# Sheet1.net
KiCad netlist of a schematic drawn in Altium Designer
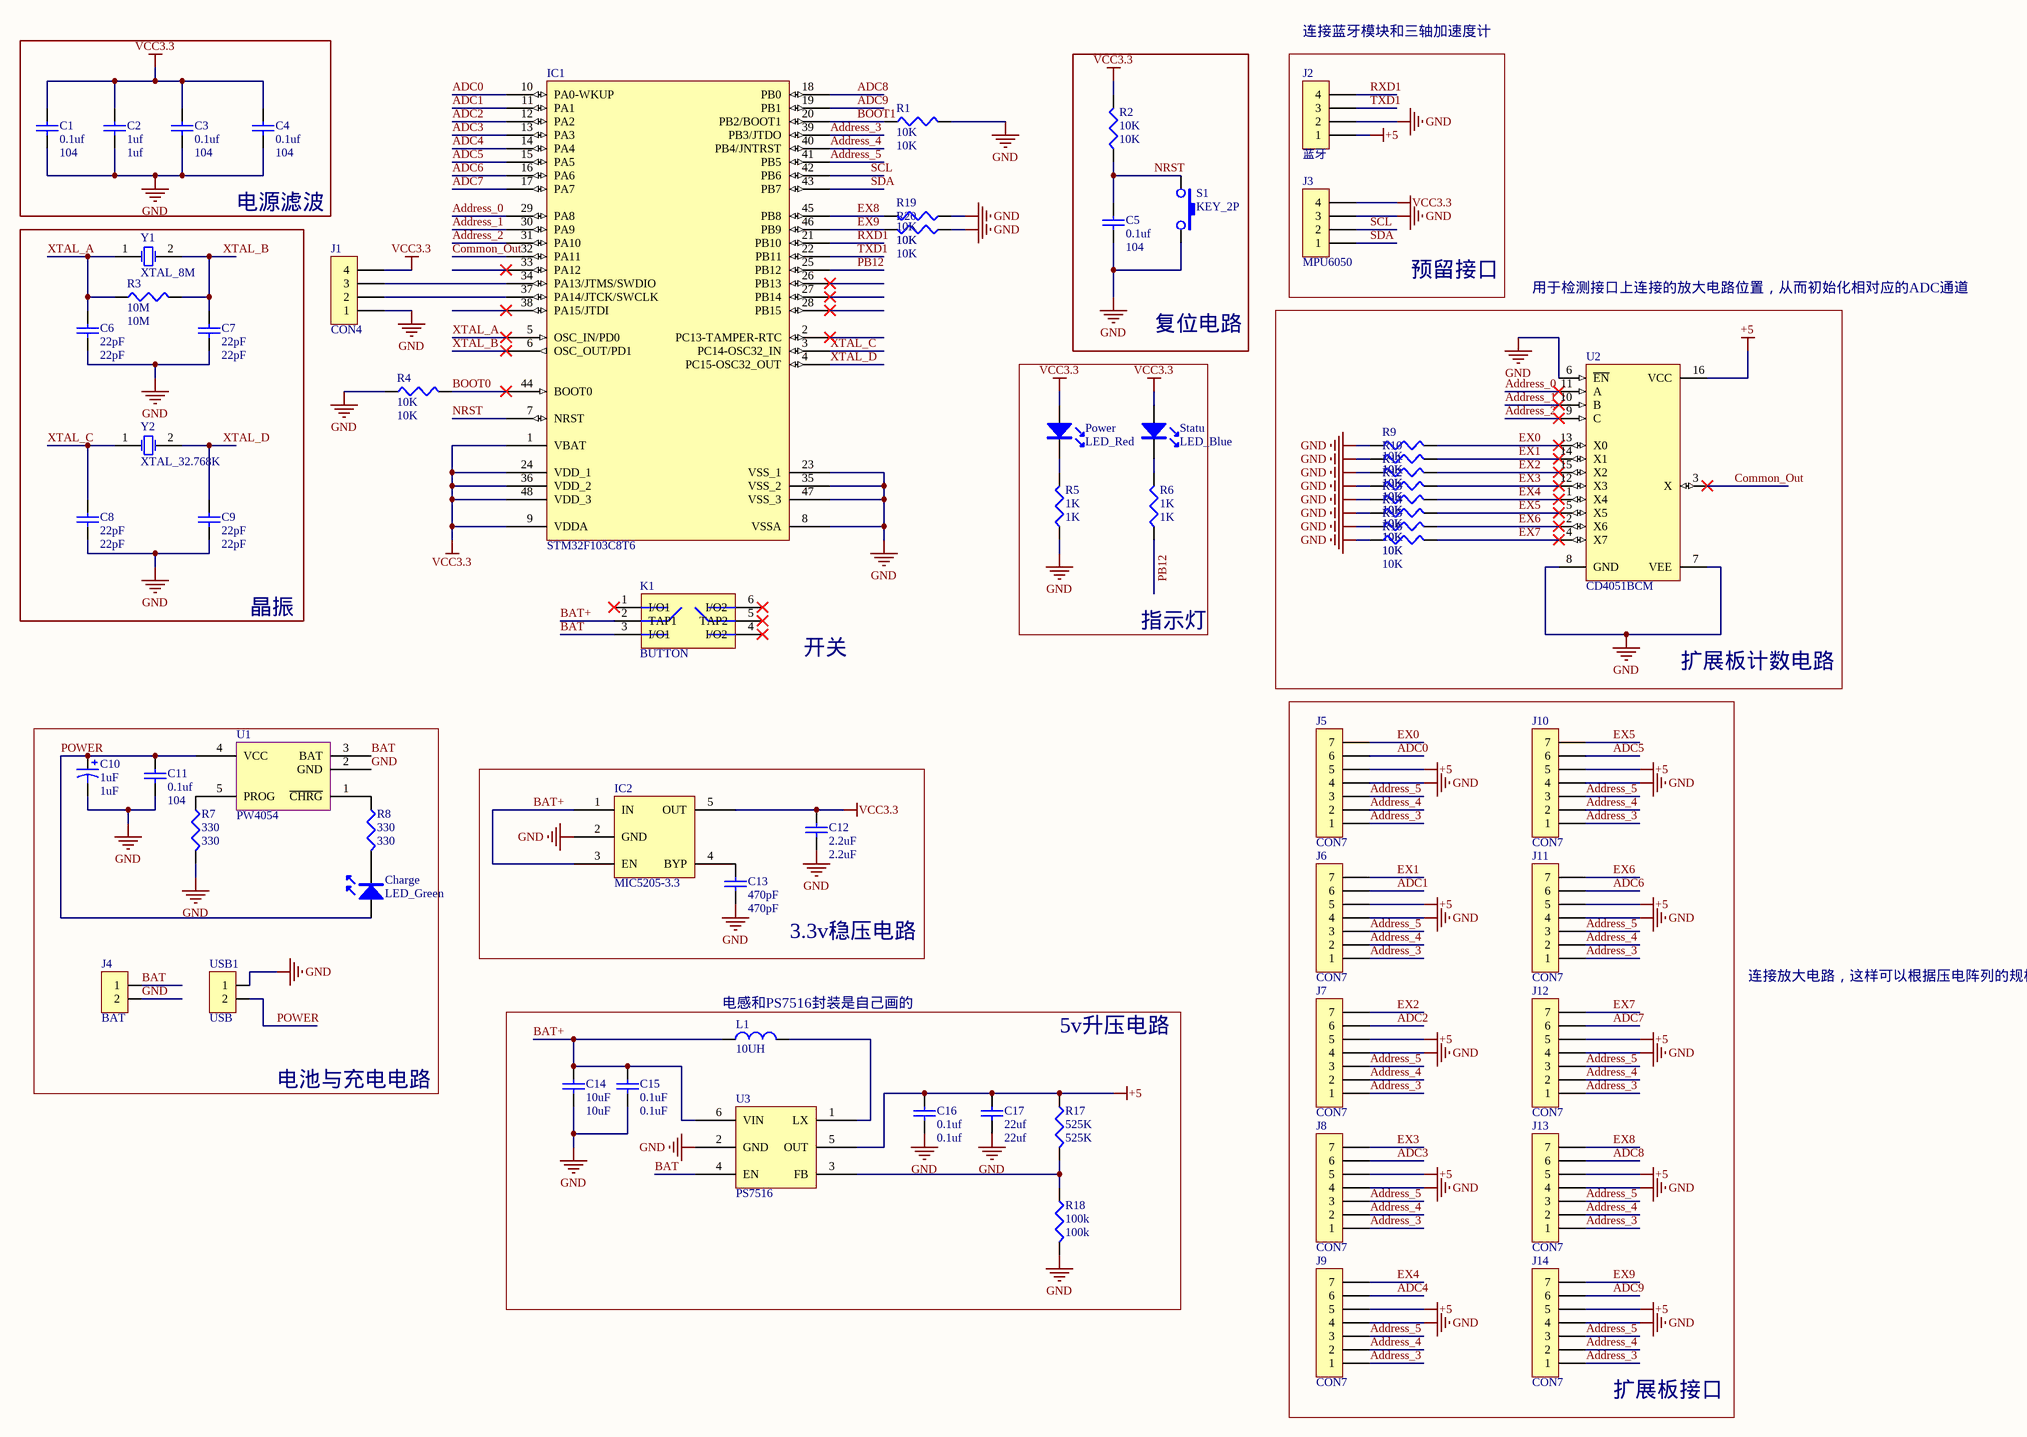
[diagram p0: Sheet1.SchDoc]

(export (version "E")
  (design (tool "Eeschema 10.0.6"))
  (components
    (comp (ref "C1")
      (value "0.1uf")
      (footprint "6-0805_L")
      (description "Capacitor (Semiconductor SIM Model)")
      (fields (field (name "ALTIUM_VALUE") "104") (field (name "PUBLISHER") "Altium Limited"))
      (libsource (lib "Miscellaneous Devices") (part "Cap Semi"))
    )
    (comp (ref "C2")
      (value "1uf")
      (footprint "6-0805_L")
      (description "Capacitor (Semiconductor SIM Model)")
      (fields (field (name "ALTIUM_VALUE") "1uf") (field (name "PUBLISHER") "Altium Limited"))
      (libsource (lib "Miscellaneous Devices") (part "Cap Semi"))
    )
    (comp (ref "C3")
      (value "0.1uf")
      (footprint "6-0805_L")
      (description "Capacitor (Semiconductor SIM Model)")
      (fields (field (name "ALTIUM_VALUE") "104") (field (name "PUBLISHER") "Altium Limited"))
      (libsource (lib "Miscellaneous Devices") (part "Cap Semi"))
    )
    (comp (ref "C4")
      (value "0.1uf")
      (footprint "6-0805_L")
      (description "Capacitor (Semiconductor SIM Model)")
      (fields (field (name "ALTIUM_VALUE") "104") (field (name "PUBLISHER") "Altium Limited"))
      (libsource (lib "Miscellaneous Devices") (part "Cap Semi"))
    )
    (comp (ref "C5")
      (value "0.1uf")
      (footprint "6-0805_L")
      (description "Capacitor (Semiconductor SIM Model)")
      (fields (field (name "ALTIUM_VALUE") "104") (field (name "PUBLISHER") "Altium Limited"))
      (libsource (lib "Miscellaneous Devices") (part "Cap Semi"))
    )
    (comp (ref "C6")
      (value "22pF")
      (footprint "6-0805_L")
      (description "Capacitor (Semiconductor SIM Model)")
      (fields (field (name "ALTIUM_VALUE") "22pF") (field (name "PUBLISHER") "Altium Limited"))
      (libsource (lib "Miscellaneous Devices") (part "Cap Semi"))
    )
    (comp (ref "C7")
      (value "22pF")
      (footprint "6-0805_L")
      (description "Capacitor (Semiconductor SIM Model)")
      (fields (field (name "ALTIUM_VALUE") "22pF") (field (name "PUBLISHER") "Altium Limited"))
      (libsource (lib "Miscellaneous Devices") (part "Cap Semi"))
    )
    (comp (ref "C8")
      (value "22pF")
      (footprint "6-0805_L")
      (description "Capacitor (Semiconductor SIM Model)")
      (fields (field (name "ALTIUM_VALUE") "22pF") (field (name "PUBLISHER") "Altium Limited"))
      (libsource (lib "Miscellaneous Devices") (part "Cap Semi"))
    )
    (comp (ref "C9")
      (value "22pF")
      (footprint "6-0805_L")
      (description "Capacitor (Semiconductor SIM Model)")
      (fields (field (name "ALTIUM_VALUE") "22pF") (field (name "PUBLISHER") "Altium Limited"))
      (libsource (lib "Miscellaneous Devices") (part "Cap Semi"))
    )
    (comp (ref "C10")
      (value "1uF")
      (footprint "C0805")
      (description "Polarized Capacitor (Surface Mount)")
      (fields (field (name "ALTIUM_VALUE") "1uF") (field (name "PUBLISHER") "Altium Limited"))
      (libsource (lib "Miscellaneous Devices") (part "Cap Pol3"))
    )
    (comp (ref "C11")
      (value "0.1uf")
      (footprint "6-0805_L")
      (description "Capacitor (Semiconductor SIM Model)")
      (fields (field (name "ALTIUM_VALUE") "104") (field (name "PUBLISHER") "Altium Limited"))
      (libsource (lib "Miscellaneous Devices") (part "Cap Semi"))
    )
    (comp (ref "C12")
      (value "2.2uF")
      (footprint "6-0805_L")
      (description "Capacitor (Semiconductor SIM Model)")
      (fields (field (name "ALTIUM_VALUE") "2.2uF") (field (name "PUBLISHER") "Altium Limited"))
      (libsource (lib "Miscellaneous Devices") (part "Cap Semi"))
    )
    (comp (ref "C13")
      (value "470pF")
      (footprint "6-0805_L")
      (description "Capacitor (Semiconductor SIM Model)")
      (fields (field (name "ALTIUM_VALUE") "470pF") (field (name "PUBLISHER") "Altium Limited"))
      (libsource (lib "Miscellaneous Devices") (part "Cap Semi"))
    )
    (comp (ref "C14")
      (value "10uF")
      (footprint "6-0805_L")
      (description "Capacitor (Semiconductor SIM Model)")
      (fields (field (name "ALTIUM_VALUE") "10uF") (field (name "PUBLISHER") "Altium Limited"))
      (libsource (lib "Miscellaneous Devices") (part "Cap Semi"))
    )
    (comp (ref "C15")
      (value "0.1uF")
      (footprint "6-0805_L")
      (description "Capacitor (Semiconductor SIM Model)")
      (fields (field (name "ALTIUM_VALUE") "0.1uF") (field (name "PUBLISHER") "Altium Limited"))
      (libsource (lib "Miscellaneous Devices") (part "Cap Semi"))
    )
    (comp (ref "C16")
      (value "0.1uf")
      (footprint "6-0805_L")
      (description "Capacitor (Semiconductor SIM Model)")
      (fields (field (name "ALTIUM_VALUE") "0.1uf") (field (name "PUBLISHER") "Altium Limited"))
      (libsource (lib "Miscellaneous Devices") (part "Cap Semi"))
    )
    (comp (ref "C17")
      (value "22uf")
      (footprint "6-0805_L")
      (description "Capacitor (Semiconductor SIM Model)")
      (fields (field (name "ALTIUM_VALUE") "22uf") (field (name "PUBLISHER") "Altium Limited"))
      (libsource (lib "Miscellaneous Devices") (part "Cap Semi"))
    )
    (comp (ref "Charge")
      (value "LED_Green")
      (footprint "6-0805_M")
      (description "LED")
      (libsource (lib "Component") (part "LED"))
    )
    (comp (ref "IC1")
      (value "STM32F103C8T6")
      (footprint "LQFP48")
      (description "单片机")
      (fields (field (name "PUBLISHER") "Altium Limited"))
      (libsource (lib "Chip") (part "STM32F103C8T6"))
    )
    (comp (ref "IC2")
      (value "MIC5205-3.3")
      (footprint "SOT-23-5")
      (description "稳压")
      (libsource (lib "Chip") (part "MIC5205-3.3"))
    )
    (comp (ref "J1")
      (value "CON4")
      (footprint "HDR1X4")
      (description "连接器")
      (libsource (lib "Connector") (part "CON4"))
    )
    (comp (ref "J2")
      (value "蓝牙")
      (footprint "HDR1X4")
      (description "Connector")
      (libsource (lib "杂元件库") (part "CON4"))
    )
    (comp (ref "J3")
      (value "MPU6050")
      (footprint "HDR1X4")
      (description "Connector")
      (libsource (lib "杂元件库") (part "CON4"))
    )
    (comp (ref "J4")
      (value "BAT")
      (footprint "HDR1X2")
      (description "Conjunctor")
      (libsource (lib "zj") (part "CON2"))
    )
    (comp (ref "J5")
      (value "CON7")
      (footprint "8P软排线")
      (description "Connector")
      (libsource (lib "杂元件库") (part "CON7"))
    )
    (comp (ref "J6")
      (value "CON7")
      (footprint "8P软排线")
      (description "Connector")
      (libsource (lib "杂元件库") (part "CON7"))
    )
    (comp (ref "J7")
      (value "CON7")
      (footprint "8P软排线")
      (description "Connector")
      (libsource (lib "杂元件库") (part "CON7"))
    )
    (comp (ref "J8")
      (value "CON7")
      (footprint "8P软排线")
      (description "Connector")
      (libsource (lib "杂元件库") (part "CON7"))
    )
    (comp (ref "J9")
      (value "CON7")
      (footprint "8P软排线")
      (description "Connector")
      (libsource (lib "杂元件库") (part "CON7"))
    )
    (comp (ref "J10")
      (value "CON7")
      (footprint "8P软排线")
      (description "Connector")
      (libsource (lib "杂元件库") (part "CON7"))
    )
    (comp (ref "J11")
      (value "CON7")
      (footprint "8P软排线")
      (description "Connector")
      (libsource (lib "杂元件库") (part "CON7"))
    )
    (comp (ref "J12")
      (value "CON7")
      (footprint "8P软排线")
      (description "Connector")
      (libsource (lib "杂元件库") (part "CON7"))
    )
    (comp (ref "J13")
      (value "CON7")
      (footprint "8P软排线")
      (description "Connector")
      (libsource (lib "杂元件库") (part "CON7"))
    )
    (comp (ref "J14")
      (value "CON7")
      (footprint "8P软排线")
      (description "Connector")
      (libsource (lib "杂元件库") (part "CON7"))
    )
    (comp (ref "K1")
      (value "BUTTON")
      (footprint "My:switch")
      (description "自锁按键")
      (libsource (lib "Component") (part "BUTTON"))
    )
    (comp (ref "L1")
      (value "10UH")
      (footprint "0850")
      (description "电感")
      (libsource (lib "Component") (part "Inductor"))
    )
    (comp (ref "Power")
      (value "LED_Red")
      (footprint "6-0805_M")
      (description "LED")
      (libsource (lib "Component") (part "LED"))
    )
    (comp (ref "R1")
      (value "10K")
      (footprint "6-0805_L")
      (description "Resistor")
      (fields (field (name "ALTIUM_VALUE") "10K") (field (name "PUBLISHER") "Altium Limited"))
      (libsource (lib "Miscellaneous Devices") (part "Res3"))
    )
    (comp (ref "R2")
      (value "10K")
      (footprint "6-0805_L")
      (description "Resistor")
      (fields (field (name "ALTIUM_VALUE") "10K") (field (name "PUBLISHER") "Altium Limited"))
      (libsource (lib "Miscellaneous Devices") (part "Res3"))
    )
    (comp (ref "R3")
      (value "10M")
      (footprint "6-0805_L")
      (description "Resistor")
      (fields (field (name "ALTIUM_VALUE") "10M") (field (name "PUBLISHER") "Altium Limited"))
      (libsource (lib "Miscellaneous Devices") (part "Res3"))
    )
    (comp (ref "R4")
      (value "10K")
      (footprint "6-0805_L")
      (description "Resistor")
      (fields (field (name "ALTIUM_VALUE") "10K") (field (name "PUBLISHER") "Altium Limited"))
      (libsource (lib "Miscellaneous Devices") (part "Res3"))
    )
    (comp (ref "R5")
      (value "1K")
      (footprint "6-0805_L")
      (description "Resistor")
      (fields (field (name "ALTIUM_VALUE") "1K") (field (name "PUBLISHER") "Altium Limited"))
      (libsource (lib "Miscellaneous Devices") (part "Res3"))
    )
    (comp (ref "R6")
      (value "1K")
      (footprint "6-0805_L")
      (description "Resistor")
      (fields (field (name "ALTIUM_VALUE") "1K") (field (name "PUBLISHER") "Altium Limited"))
      (libsource (lib "Miscellaneous Devices") (part "Res3"))
    )
    (comp (ref "R7")
      (value "330")
      (footprint "6-0805_L")
      (description "Resistor")
      (fields (field (name "ALTIUM_VALUE") "330") (field (name "PUBLISHER") "Altium Limited"))
      (libsource (lib "Miscellaneous Devices") (part "Res3"))
    )
    (comp (ref "R8")
      (value "330")
      (footprint "6-0805_L")
      (description "Resistor")
      (fields (field (name "ALTIUM_VALUE") "330") (field (name "PUBLISHER") "Altium Limited"))
      (libsource (lib "Miscellaneous Devices") (part "Res3"))
    )
    (comp (ref "R9")
      (value "10K")
      (footprint "6-0805_L")
      (description "Resistor")
      (fields (field (name "ALTIUM_VALUE") "10K") (field (name "PUBLISHER") "Altium Limited"))
      (libsource (lib "Miscellaneous Devices") (part "Res3"))
    )
    (comp (ref "R10")
      (value "10K")
      (footprint "6-0805_L")
      (description "Resistor")
      (fields (field (name "ALTIUM_VALUE") "10K") (field (name "PUBLISHER") "Altium Limited"))
      (libsource (lib "Miscellaneous Devices") (part "Res3"))
    )
    (comp (ref "R11")
      (value "10K")
      (footprint "6-0805_L")
      (description "Resistor")
      (fields (field (name "ALTIUM_VALUE") "10K") (field (name "PUBLISHER") "Altium Limited"))
      (libsource (lib "Miscellaneous Devices") (part "Res3"))
    )
    (comp (ref "R12")
      (value "10K")
      (footprint "6-0805_L")
      (description "Resistor")
      (fields (field (name "ALTIUM_VALUE") "10K") (field (name "PUBLISHER") "Altium Limited"))
      (libsource (lib "Miscellaneous Devices") (part "Res3"))
    )
    (comp (ref "R13")
      (value "10K")
      (footprint "6-0805_L")
      (description "Resistor")
      (fields (field (name "ALTIUM_VALUE") "10K") (field (name "PUBLISHER") "Altium Limited"))
      (libsource (lib "Miscellaneous Devices") (part "Res3"))
    )
    (comp (ref "R14")
      (value "10K")
      (footprint "6-0805_L")
      (description "Resistor")
      (fields (field (name "ALTIUM_VALUE") "10K") (field (name "PUBLISHER") "Altium Limited"))
      (libsource (lib "Miscellaneous Devices") (part "Res3"))
    )
    (comp (ref "R15")
      (value "10K")
      (footprint "6-0805_L")
      (description "Resistor")
      (fields (field (name "ALTIUM_VALUE") "10K") (field (name "PUBLISHER") "Altium Limited"))
      (libsource (lib "Miscellaneous Devices") (part "Res3"))
    )
    (comp (ref "R16")
      (value "10K")
      (footprint "6-0805_L")
      (description "Resistor")
      (fields (field (name "ALTIUM_VALUE") "10K") (field (name "PUBLISHER") "Altium Limited"))
      (libsource (lib "Miscellaneous Devices") (part "Res3"))
    )
    (comp (ref "R17")
      (value "525K")
      (footprint "6-0805_L")
      (description "Resistor")
      (fields (field (name "ALTIUM_VALUE") "525K") (field (name "PUBLISHER") "Altium Limited"))
      (libsource (lib "Miscellaneous Devices") (part "Res3"))
    )
    (comp (ref "R18")
      (value "100k")
      (footprint "6-0805_L")
      (description "Resistor")
      (fields (field (name "ALTIUM_VALUE") "100k") (field (name "PUBLISHER") "Altium Limited"))
      (libsource (lib "Miscellaneous Devices") (part "Res3"))
    )
    (comp (ref "R19")
      (value "10K")
      (footprint "6-0805_L")
      (description "Resistor")
      (fields (field (name "ALTIUM_VALUE") "10K") (field (name "PUBLISHER") "Altium Limited"))
      (libsource (lib "Miscellaneous Devices") (part "Res3"))
    )
    (comp (ref "R20")
      (value "10K")
      (footprint "6-0805_L")
      (description "Resistor")
      (fields (field (name "ALTIUM_VALUE") "10K") (field (name "PUBLISHER") "Altium Limited"))
      (libsource (lib "Miscellaneous Devices") (part "Res3"))
    )
    (comp (ref "S1")
      (value "KEY_2P")
      (footprint "My:button")
      (description "轻触按键2P")
      (libsource (lib "Component") (part "KEY_2P"))
    )
    (comp (ref "Statu")
      (value "LED_Blue")
      (footprint "6-0805_M")
      (description "LED")
      (libsource (lib "Component") (part "LED"))
    )
    (comp (ref "U1") (value "PW4054") (footprint "SOT-23-CT5_L") (libsource (lib "Schlib") (part "PW4054")))
    (comp (ref "U2")
      (value "CD4051BCM")
      (footprint "M16A_N")
      (description "8-Channel Analog Multiplexer/Demultiplexer")
      (fields (field (name "PUBLISHER") "Altium Limited"))
      (libsource (lib "altium-import") (part "root_0_CD4051BCM_"))
    )
    (comp (ref "U3")
      (value "PS7516")
      (footprint "SOT23-6_M")
      (libsource (lib "Integrated_Library1") (part "PS7516"))
    )
    (comp (ref "USB1")
      (value "USB")
      (footprint "Type-C")
      (description "Conjunctor")
      (libsource (lib "zj") (part "CON2"))
    )
    (comp (ref "Y1")
      (value "XTAL_8M")
      (footprint "xtal")
      (description "Crystal Oscillator")
      (fields (field (name "PUBLISHER") "Altium Limited"))
      (libsource (lib "Miscellaneous Devices") (part "XTAL"))
    )
    (comp (ref "Y2")
      (value "XTAL_32.768K")
      (footprint "R38")
      (description "Crystal Oscillator")
      (fields (field (name "PUBLISHER") "Altium Limited"))
      (libsource (lib "Miscellaneous Devices") (part "XTAL"))
    )
  )
  (nets
    (net (code "1") (name "+5") (class "Default")
      (node (ref "C16") (pin "2") (pinfunction "2_2") (pintype "passive"))
      (node (ref "C17") (pin "2") (pinfunction "2_2") (pintype "passive"))
      (node (ref "J10") (pin "5") (pinfunction "5_5") (pintype "passive"))
      (node (ref "J11") (pin "5") (pinfunction "5_5") (pintype "passive"))
      (node (ref "J12") (pin "5") (pinfunction "5_5") (pintype "passive"))
      (node (ref "J13") (pin "5") (pinfunction "5_5") (pintype "passive"))
      (node (ref "J14") (pin "5") (pinfunction "5_5") (pintype "passive"))
      (node (ref "J2") (pin "1") (pinfunction "1_1") (pintype "passive"))
      (node (ref "J5") (pin "5") (pinfunction "5_5") (pintype "passive"))
      (node (ref "J6") (pin "5") (pinfunction "5_5") (pintype "passive"))
      (node (ref "J7") (pin "5") (pinfunction "5_5") (pintype "passive"))
      (node (ref "J8") (pin "5") (pinfunction "5_5") (pintype "passive"))
      (node (ref "J9") (pin "5") (pinfunction "5_5") (pintype "passive"))
      (node (ref "R17") (pin "1") (pinfunction "1_1") (pintype "passive"))
      (node (ref "U2") (pin "16") (pinfunction "VCC_16") (pintype "power_in"))
      (node (ref "U3") (pin "5") (pinfunction "OUT_5") (pintype "passive"))
    )
    (net (code "2") (name "/ADC0") (class "Default")
      (node (ref "IC1") (pin "10") (pinfunction "PA0-WKUP_10") (pintype "bidirectional"))
      (node (ref "J5") (pin "6") (pinfunction "6_6") (pintype "passive"))
    )
    (net (code "3") (name "/ADC1") (class "Default")
      (node (ref "IC1") (pin "11") (pinfunction "PA1_11") (pintype "bidirectional"))
      (node (ref "J6") (pin "6") (pinfunction "6_6") (pintype "passive"))
    )
    (net (code "4") (name "/ADC2") (class "Default")
      (node (ref "IC1") (pin "12") (pinfunction "PA2_12") (pintype "bidirectional"))
      (node (ref "J7") (pin "6") (pinfunction "6_6") (pintype "passive"))
    )
    (net (code "5") (name "/ADC3") (class "Default")
      (node (ref "IC1") (pin "13") (pinfunction "PA3_13") (pintype "bidirectional"))
      (node (ref "J8") (pin "6") (pinfunction "6_6") (pintype "passive"))
    )
    (net (code "6") (name "/ADC4") (class "Default")
      (node (ref "IC1") (pin "14") (pinfunction "PA4_14") (pintype "bidirectional"))
      (node (ref "J9") (pin "6") (pinfunction "6_6") (pintype "passive"))
    )
    (net (code "7") (name "/ADC5") (class "Default")
      (node (ref "IC1") (pin "15") (pinfunction "PA5_15") (pintype "bidirectional"))
      (node (ref "J10") (pin "6") (pinfunction "6_6") (pintype "passive"))
    )
    (net (code "8") (name "/ADC6") (class "Default")
      (node (ref "IC1") (pin "16") (pinfunction "PA6_16") (pintype "bidirectional"))
      (node (ref "J11") (pin "6") (pinfunction "6_6") (pintype "passive"))
    )
    (net (code "9") (name "/ADC7") (class "Default")
      (node (ref "IC1") (pin "17") (pinfunction "PA7_17") (pintype "bidirectional"))
      (node (ref "J12") (pin "6") (pinfunction "6_6") (pintype "passive"))
    )
    (net (code "10") (name "/ADC8") (class "Default")
      (node (ref "IC1") (pin "18") (pinfunction "PB0_18") (pintype "bidirectional"))
      (node (ref "J13") (pin "6") (pinfunction "6_6") (pintype "passive"))
    )
    (net (code "11") (name "/ADC9") (class "Default")
      (node (ref "IC1") (pin "19") (pinfunction "PB1_19") (pintype "bidirectional"))
      (node (ref "J14") (pin "6") (pinfunction "6_6") (pintype "passive"))
    )
    (net (code "12") (name "/Address_0") (class "Default")
      (node (ref "IC1") (pin "29") (pinfunction "PA8_29") (pintype "bidirectional"))
      (node (ref "U2") (pin "11") (pinfunction "A_11") (pintype "input"))
    )
    (net (code "13") (name "/Address_1") (class "Default")
      (node (ref "IC1") (pin "30") (pinfunction "PA9_30") (pintype "bidirectional"))
      (node (ref "U2") (pin "10") (pinfunction "B_10") (pintype "input"))
    )
    (net (code "14") (name "/Address_2") (class "Default")
      (node (ref "IC1") (pin "31") (pinfunction "PA10_31") (pintype "bidirectional"))
      (node (ref "U2") (pin "9") (pinfunction "C_9") (pintype "input"))
    )
    (net (code "15") (name "/Address_3") (class "Default")
      (node (ref "IC1") (pin "39") (pinfunction "PB3/JTDO_39") (pintype "bidirectional"))
      (node (ref "J10") (pin "1") (pinfunction "1_1") (pintype "passive"))
      (node (ref "J11") (pin "1") (pinfunction "1_1") (pintype "passive"))
      (node (ref "J12") (pin "1") (pinfunction "1_1") (pintype "passive"))
      (node (ref "J13") (pin "1") (pinfunction "1_1") (pintype "passive"))
      (node (ref "J14") (pin "1") (pinfunction "1_1") (pintype "passive"))
      (node (ref "J5") (pin "1") (pinfunction "1_1") (pintype "passive"))
      (node (ref "J6") (pin "1") (pinfunction "1_1") (pintype "passive"))
      (node (ref "J7") (pin "1") (pinfunction "1_1") (pintype "passive"))
      (node (ref "J8") (pin "1") (pinfunction "1_1") (pintype "passive"))
      (node (ref "J9") (pin "1") (pinfunction "1_1") (pintype "passive"))
    )
    (net (code "16") (name "/Address_4") (class "Default")
      (node (ref "IC1") (pin "40") (pinfunction "PB4/JNTRST_40") (pintype "bidirectional"))
      (node (ref "J10") (pin "2") (pinfunction "2_2") (pintype "passive"))
      (node (ref "J11") (pin "2") (pinfunction "2_2") (pintype "passive"))
      (node (ref "J12") (pin "2") (pinfunction "2_2") (pintype "passive"))
      (node (ref "J13") (pin "2") (pinfunction "2_2") (pintype "passive"))
      (node (ref "J14") (pin "2") (pinfunction "2_2") (pintype "passive"))
      (node (ref "J5") (pin "2") (pinfunction "2_2") (pintype "passive"))
      (node (ref "J6") (pin "2") (pinfunction "2_2") (pintype "passive"))
      (node (ref "J7") (pin "2") (pinfunction "2_2") (pintype "passive"))
      (node (ref "J8") (pin "2") (pinfunction "2_2") (pintype "passive"))
      (node (ref "J9") (pin "2") (pinfunction "2_2") (pintype "passive"))
    )
    (net (code "17") (name "/Address_5") (class "Default")
      (node (ref "IC1") (pin "41") (pinfunction "PB5_41") (pintype "bidirectional"))
      (node (ref "J10") (pin "3") (pinfunction "3_3") (pintype "passive"))
      (node (ref "J11") (pin "3") (pinfunction "3_3") (pintype "passive"))
      (node (ref "J12") (pin "3") (pinfunction "3_3") (pintype "passive"))
      (node (ref "J13") (pin "3") (pinfunction "3_3") (pintype "passive"))
      (node (ref "J14") (pin "3") (pinfunction "3_3") (pintype "passive"))
      (node (ref "J5") (pin "3") (pinfunction "3_3") (pintype "passive"))
      (node (ref "J6") (pin "3") (pinfunction "3_3") (pintype "passive"))
      (node (ref "J7") (pin "3") (pinfunction "3_3") (pintype "passive"))
      (node (ref "J8") (pin "3") (pinfunction "3_3") (pintype "passive"))
      (node (ref "J9") (pin "3") (pinfunction "3_3") (pintype "passive"))
    )
    (net (code "18") (name "/BAT") (class "Default")
      (node (ref "J4") (pin "1") (pinfunction "1_1") (pintype "passive"))
      (node (ref "K1") (pin "3") (pinfunction "I/O1_3") (pintype "passive"))
      (node (ref "U1") (pin "3") (pinfunction "BAT_3") (pintype "passive"))
      (node (ref "U3") (pin "4") (pinfunction "EN_4") (pintype "passive"))
    )
    (net (code "19") (name "/BAT+") (class "Default")
      (node (ref "C14") (pin "2") (pinfunction "2_2") (pintype "passive"))
      (node (ref "C15") (pin "2") (pinfunction "2_2") (pintype "passive"))
      (node (ref "IC2") (pin "1") (pinfunction "IN_1") (pintype "passive"))
      (node (ref "IC2") (pin "3") (pinfunction "EN_3") (pintype "passive"))
      (node (ref "K1") (pin "2") (pinfunction "TAP1_2") (pintype "passive"))
      (node (ref "L1") (pin "1") (pinfunction "1_1") (pintype "passive"))
      (node (ref "U3") (pin "6") (pinfunction "VIN_6") (pintype "passive"))
    )
    (net (code "20") (name "/BOOT0") (class "Default")
      (node (ref "IC1") (pin "44") (pinfunction "BOOT0_44") (pintype "input"))
      (node (ref "R4") (pin "2") (pinfunction "2_2") (pintype "passive"))
    )
    (net (code "21") (name "/BOOT1") (class "Default")
      (node (ref "IC1") (pin "20") (pinfunction "PB2/BOOT1_20") (pintype "bidirectional"))
      (node (ref "R1") (pin "1") (pinfunction "1_1") (pintype "passive"))
    )
    (net (code "22") (name "/Common_Out") (class "Default")
      (node (ref "IC1") (pin "32") (pinfunction "PA11_32") (pintype "bidirectional"))
      (node (ref "U2") (pin "3") (pinfunction "X_3") (pintype "bidirectional"))
    )
    (net (code "23") (name "/EX0") (class "Default")
      (node (ref "J5") (pin "7") (pinfunction "7_7") (pintype "passive"))
      (node (ref "R9") (pin "2") (pinfunction "2_2") (pintype "passive"))
      (node (ref "U2") (pin "13") (pinfunction "X0_13") (pintype "bidirectional"))
    )
    (net (code "24") (name "/EX1") (class "Default")
      (node (ref "J6") (pin "7") (pinfunction "7_7") (pintype "passive"))
      (node (ref "R10") (pin "2") (pinfunction "2_2") (pintype "passive"))
      (node (ref "U2") (pin "14") (pinfunction "X1_14") (pintype "bidirectional"))
    )
    (net (code "25") (name "/EX2") (class "Default")
      (node (ref "J7") (pin "7") (pinfunction "7_7") (pintype "passive"))
      (node (ref "R11") (pin "2") (pinfunction "2_2") (pintype "passive"))
      (node (ref "U2") (pin "15") (pinfunction "X2_15") (pintype "bidirectional"))
    )
    (net (code "26") (name "/EX3") (class "Default")
      (node (ref "J8") (pin "7") (pinfunction "7_7") (pintype "passive"))
      (node (ref "R12") (pin "2") (pinfunction "2_2") (pintype "passive"))
      (node (ref "U2") (pin "12") (pinfunction "X3_12") (pintype "bidirectional"))
    )
    (net (code "27") (name "/EX4") (class "Default")
      (node (ref "J9") (pin "7") (pinfunction "7_7") (pintype "passive"))
      (node (ref "R13") (pin "2") (pinfunction "2_2") (pintype "passive"))
      (node (ref "U2") (pin "1") (pinfunction "X4_1") (pintype "bidirectional"))
    )
    (net (code "28") (name "/EX5") (class "Default")
      (node (ref "J10") (pin "7") (pinfunction "7_7") (pintype "passive"))
      (node (ref "R14") (pin "2") (pinfunction "2_2") (pintype "passive"))
      (node (ref "U2") (pin "5") (pinfunction "X5_5") (pintype "bidirectional"))
    )
    (net (code "29") (name "/EX6") (class "Default")
      (node (ref "J11") (pin "7") (pinfunction "7_7") (pintype "passive"))
      (node (ref "R15") (pin "2") (pinfunction "2_2") (pintype "passive"))
      (node (ref "U2") (pin "2") (pinfunction "X6_2") (pintype "bidirectional"))
    )
    (net (code "30") (name "/EX7") (class "Default")
      (node (ref "J12") (pin "7") (pinfunction "7_7") (pintype "passive"))
      (node (ref "R16") (pin "2") (pinfunction "2_2") (pintype "passive"))
      (node (ref "U2") (pin "4") (pinfunction "X7_4") (pintype "bidirectional"))
    )
    (net (code "31") (name "/EX8") (class "Default")
      (node (ref "IC1") (pin "45") (pinfunction "PB8_45") (pintype "bidirectional"))
      (node (ref "J13") (pin "7") (pinfunction "7_7") (pintype "passive"))
      (node (ref "R19") (pin "2") (pinfunction "2_2") (pintype "passive"))
    )
    (net (code "32") (name "/EX9") (class "Default")
      (node (ref "IC1") (pin "46") (pinfunction "PB9_46") (pintype "bidirectional"))
      (node (ref "J14") (pin "7") (pinfunction "7_7") (pintype "passive"))
      (node (ref "R20") (pin "2") (pinfunction "2_2") (pintype "passive"))
    )
    (net (code "33") (name "/NRST") (class "Default")
      (node (ref "C5") (pin "2") (pinfunction "2_2") (pintype "passive"))
      (node (ref "IC1") (pin "7") (pinfunction "NRST_7") (pintype "bidirectional"))
      (node (ref "R2") (pin "1") (pinfunction "1_1") (pintype "passive"))
      (node (ref "S1") (pin "1") (pinfunction "1_1") (pintype "passive"))
    )
    (net (code "34") (name "/PB12") (class "Default")
      (node (ref "IC1") (pin "25") (pinfunction "PB12_25") (pintype "bidirectional"))
      (node (ref "R6") (pin "1") (pinfunction "1_1") (pintype "passive"))
    )
    (net (code "35") (name "/POWER") (class "Default")
      (node (ref "C10") (pin "1") (pinfunction "1_1") (pintype "passive"))
      (node (ref "C11") (pin "2") (pinfunction "2_2") (pintype "passive"))
      (node (ref "Charge") (pin "1") (pinfunction "1_1") (pintype "passive"))
      (node (ref "U1") (pin "4") (pinfunction "VCC_4") (pintype "passive"))
      (node (ref "USB1") (pin "2") (pinfunction "2_2") (pintype "passive"))
    )
    (net (code "36") (name "/RXD1") (class "Default")
      (node (ref "IC1") (pin "21") (pinfunction "PB10_21") (pintype "bidirectional"))
      (node (ref "J2") (pin "4") (pinfunction "4_4") (pintype "passive"))
    )
    (net (code "37") (name "/SCL") (class "Default")
      (node (ref "IC1") (pin "42") (pinfunction "PB6_42") (pintype "bidirectional"))
      (node (ref "J3") (pin "2") (pinfunction "2_2") (pintype "passive"))
    )
    (net (code "38") (name "/SDA") (class "Default")
      (node (ref "IC1") (pin "43") (pinfunction "PB7_43") (pintype "bidirectional"))
      (node (ref "J3") (pin "1") (pinfunction "1_1") (pintype "passive"))
    )
    (net (code "39") (name "/TXD1") (class "Default")
      (node (ref "IC1") (pin "22") (pinfunction "PB11_22") (pintype "bidirectional"))
      (node (ref "J2") (pin "3") (pinfunction "3_3") (pintype "passive"))
    )
    (net (code "40") (name "/XTAL_A") (class "Default")
      (node (ref "C6") (pin "2") (pinfunction "2_2") (pintype "passive"))
      (node (ref "IC1") (pin "5") (pinfunction "OSC_IN/PD0_5") (pintype "input"))
      (node (ref "R3") (pin "1") (pinfunction "1_1") (pintype "passive"))
      (node (ref "Y1") (pin "1") (pinfunction "OSC1_1") (pintype "passive"))
    )
    (net (code "41") (name "/XTAL_B") (class "Default")
      (node (ref "C7") (pin "2") (pinfunction "2_2") (pintype "passive"))
      (node (ref "IC1") (pin "6") (pinfunction "OSC_OUT/PD1_6") (pintype "output"))
      (node (ref "R3") (pin "2") (pinfunction "2_2") (pintype "passive"))
      (node (ref "Y1") (pin "2") (pinfunction "OSC2_2") (pintype "passive"))
    )
    (net (code "42") (name "/XTAL_C") (class "Default")
      (node (ref "C8") (pin "2") (pinfunction "2_2") (pintype "passive"))
      (node (ref "IC1") (pin "3") (pinfunction "PC14-OSC32_IN_3") (pintype "bidirectional"))
      (node (ref "Y2") (pin "1") (pinfunction "OSC1_1") (pintype "passive"))
    )
    (net (code "43") (name "/XTAL_D") (class "Default")
      (node (ref "C9") (pin "2") (pinfunction "2_2") (pintype "passive"))
      (node (ref "IC1") (pin "4") (pinfunction "PC15-OSC32_OUT_4") (pintype "bidirectional"))
      (node (ref "Y2") (pin "2") (pinfunction "OSC2_2") (pintype "passive"))
    )
    (net (code "44") (name "GND") (class "Default")
      (node (ref "C1") (pin "1") (pinfunction "1_1") (pintype "passive"))
      (node (ref "C10") (pin "2") (pinfunction "2_2") (pintype "passive"))
      (node (ref "C11") (pin "1") (pinfunction "1_1") (pintype "passive"))
      (node (ref "C12") (pin "1") (pinfunction "1_1") (pintype "passive"))
      (node (ref "C13") (pin "1") (pinfunction "1_1") (pintype "passive"))
      (node (ref "C14") (pin "1") (pinfunction "1_1") (pintype "passive"))
      (node (ref "C15") (pin "1") (pinfunction "1_1") (pintype "passive"))
      (node (ref "C16") (pin "1") (pinfunction "1_1") (pintype "passive"))
      (node (ref "C17") (pin "1") (pinfunction "1_1") (pintype "passive"))
      (node (ref "C2") (pin "1") (pinfunction "1_1") (pintype "passive"))
      (node (ref "C3") (pin "1") (pinfunction "1_1") (pintype "passive"))
      (node (ref "C4") (pin "1") (pinfunction "1_1") (pintype "passive"))
      (node (ref "C5") (pin "1") (pinfunction "1_1") (pintype "passive"))
      (node (ref "C6") (pin "1") (pinfunction "1_1") (pintype "passive"))
      (node (ref "C7") (pin "1") (pinfunction "1_1") (pintype "passive"))
      (node (ref "C8") (pin "1") (pinfunction "1_1") (pintype "passive"))
      (node (ref "C9") (pin "1") (pinfunction "1_1") (pintype "passive"))
      (node (ref "IC1") (pin "23") (pinfunction "VSS_1_23") (pintype "power_in"))
      (node (ref "IC1") (pin "35") (pinfunction "VSS_2_35") (pintype "power_in"))
      (node (ref "IC1") (pin "47") (pinfunction "VSS_3_47") (pintype "power_in"))
      (node (ref "IC1") (pin "8") (pinfunction "VSSA_8") (pintype "power_in"))
      (node (ref "IC2") (pin "2") (pinfunction "GND_2") (pintype "passive"))
      (node (ref "J1") (pin "1") (pinfunction "1_1") (pintype "passive"))
      (node (ref "J10") (pin "4") (pinfunction "4_4") (pintype "passive"))
      (node (ref "J11") (pin "4") (pinfunction "4_4") (pintype "passive"))
      (node (ref "J12") (pin "4") (pinfunction "4_4") (pintype "passive"))
      (node (ref "J13") (pin "4") (pinfunction "4_4") (pintype "passive"))
      (node (ref "J14") (pin "4") (pinfunction "4_4") (pintype "passive"))
      (node (ref "J2") (pin "2") (pinfunction "2_2") (pintype "passive"))
      (node (ref "J3") (pin "3") (pinfunction "3_3") (pintype "passive"))
      (node (ref "J4") (pin "2") (pinfunction "2_2") (pintype "passive"))
      (node (ref "J5") (pin "4") (pinfunction "4_4") (pintype "passive"))
      (node (ref "J6") (pin "4") (pinfunction "4_4") (pintype "passive"))
      (node (ref "J7") (pin "4") (pinfunction "4_4") (pintype "passive"))
      (node (ref "J8") (pin "4") (pinfunction "4_4") (pintype "passive"))
      (node (ref "J9") (pin "4") (pinfunction "4_4") (pintype "passive"))
      (node (ref "R1") (pin "2") (pinfunction "2_2") (pintype "passive"))
      (node (ref "R10") (pin "1") (pinfunction "1_1") (pintype "passive"))
      (node (ref "R11") (pin "1") (pinfunction "1_1") (pintype "passive"))
      (node (ref "R12") (pin "1") (pinfunction "1_1") (pintype "passive"))
      (node (ref "R13") (pin "1") (pinfunction "1_1") (pintype "passive"))
      (node (ref "R14") (pin "1") (pinfunction "1_1") (pintype "passive"))
      (node (ref "R15") (pin "1") (pinfunction "1_1") (pintype "passive"))
      (node (ref "R16") (pin "1") (pinfunction "1_1") (pintype "passive"))
      (node (ref "R18") (pin "2") (pinfunction "2_2") (pintype "passive"))
      (node (ref "R19") (pin "1") (pinfunction "1_1") (pintype "passive"))
      (node (ref "R20") (pin "1") (pinfunction "1_1") (pintype "passive"))
      (node (ref "R4") (pin "1") (pinfunction "1_1") (pintype "passive"))
      (node (ref "R5") (pin "1") (pinfunction "1_1") (pintype "passive"))
      (node (ref "R7") (pin "2") (pinfunction "2_2") (pintype "passive"))
      (node (ref "R9") (pin "1") (pinfunction "1_1") (pintype "passive"))
      (node (ref "S1") (pin "2") (pinfunction "2_2") (pintype "passive"))
      (node (ref "U1") (pin "2") (pinfunction "GND_2") (pintype "passive"))
      (node (ref "U2") (pin "6") (pinfunction "~{EN}_6") (pintype "input"))
      (node (ref "U2") (pin "7") (pinfunction "VEE_7") (pintype "power_in"))
      (node (ref "U2") (pin "8") (pinfunction "GND_8") (pintype "power_in"))
      (node (ref "U3") (pin "2") (pinfunction "GND_2") (pintype "passive"))
      (node (ref "USB1") (pin "1") (pinfunction "1_1") (pintype "passive"))
    )
    (net (code "45") (name "Net-(Charge-Pad2)") (class "Default")
      (node (ref "Charge") (pin "2") (pinfunction "2_2") (pintype "passive"))
      (node (ref "R8") (pin "2") (pinfunction "2_2") (pintype "passive"))
    )
    (net (code "46") (name "Net-(IC1-PA13{slash}JTMS{slash}SWDIO)") (class "Default")
      (node (ref "IC1") (pin "34") (pinfunction "PA13/JTMS/SWDIO_34") (pintype "bidirectional"))
      (node (ref "J1") (pin "3") (pinfunction "3_3") (pintype "passive"))
    )
    (net (code "47") (name "Net-(IC1-PA14{slash}JTCK{slash}SWCLK)") (class "Default")
      (node (ref "IC1") (pin "37") (pinfunction "PA14/JTCK/SWCLK_37") (pintype "bidirectional"))
      (node (ref "J1") (pin "2") (pinfunction "2_2") (pintype "passive"))
    )
    (net (code "48") (name "Net-(IC2-BYP)") (class "Default")
      (node (ref "C13") (pin "2") (pinfunction "2_2") (pintype "passive"))
      (node (ref "IC2") (pin "4") (pinfunction "BYP_4") (pintype "passive"))
    )
    (net (code "49") (name "Net-(Power-Pad2)") (class "Default")
      (node (ref "Power") (pin "2") (pinfunction "2_2") (pintype "passive"))
      (node (ref "R5") (pin "2") (pinfunction "2_2") (pintype "passive"))
    )
    (net (code "50") (name "Net-(R6-Pad2)") (class "Default")
      (node (ref "R6") (pin "2") (pinfunction "2_2") (pintype "passive"))
      (node (ref "Statu") (pin "2") (pinfunction "2_2") (pintype "passive"))
    )
    (net (code "51") (name "Net-(U1-PROG)") (class "Default")
      (node (ref "R7") (pin "1") (pinfunction "1_1") (pintype "passive"))
      (node (ref "U1") (pin "5") (pinfunction "PROG_5") (pintype "passive"))
    )
    (net (code "52") (name "Net-(U1-~{CHRG})") (class "Default")
      (node (ref "R8") (pin "1") (pinfunction "1_1") (pintype "passive"))
      (node (ref "U1") (pin "1") (pinfunction "~{CHRG}_1") (pintype "passive"))
    )
    (net (code "53") (name "Net-(U3-FB)") (class "Default")
      (node (ref "R17") (pin "2") (pinfunction "2_2") (pintype "passive"))
      (node (ref "R18") (pin "1") (pinfunction "1_1") (pintype "passive"))
      (node (ref "U3") (pin "3") (pinfunction "FB_3") (pintype "passive"))
    )
    (net (code "54") (name "Net-(U3-LX)") (class "Default")
      (node (ref "L1") (pin "2") (pinfunction "2_2") (pintype "passive"))
      (node (ref "U3") (pin "1") (pinfunction "LX_1") (pintype "passive"))
    )
    (net (code "55") (name "VCC3.3") (class "Default")
      (node (ref "C1") (pin "2") (pinfunction "2_2") (pintype "passive"))
      (node (ref "C12") (pin "2") (pinfunction "2_2") (pintype "passive"))
      (node (ref "C2") (pin "2") (pinfunction "2_2") (pintype "passive"))
      (node (ref "C3") (pin "2") (pinfunction "2_2") (pintype "passive"))
      (node (ref "C4") (pin "2") (pinfunction "2_2") (pintype "passive"))
      (node (ref "IC1") (pin "1") (pinfunction "VBAT_1") (pintype "power_in"))
      (node (ref "IC1") (pin "24") (pinfunction "VDD_1_24") (pintype "power_in"))
      (node (ref "IC1") (pin "36") (pinfunction "VDD_2_36") (pintype "power_in"))
      (node (ref "IC1") (pin "48") (pinfunction "VDD_3_48") (pintype "power_in"))
      (node (ref "IC1") (pin "9") (pinfunction "VDDA_9") (pintype "power_in"))
      (node (ref "IC2") (pin "5") (pinfunction "OUT_5") (pintype "passive"))
      (node (ref "J1") (pin "4") (pinfunction "4_4") (pintype "passive"))
      (node (ref "J3") (pin "4") (pinfunction "4_4") (pintype "passive"))
      (node (ref "Power") (pin "1") (pinfunction "1_1") (pintype "passive"))
      (node (ref "R2") (pin "2") (pinfunction "2_2") (pintype "passive"))
      (node (ref "Statu") (pin "1") (pinfunction "1_1") (pintype "passive"))
    )
    (net (code "56") (name "unconnected-(IC1-PA12-Pad33)") (class "Default")
      (node (ref "IC1") (pin "33") (pinfunction "PA12_33") (pintype "bidirectional+no_connect"))
    )
    (net (code "57") (name "unconnected-(IC1-PA15{slash}JTDI-Pad38)") (class "Default")
      (node (ref "IC1") (pin "38") (pinfunction "PA15/JTDI_38") (pintype "bidirectional+no_connect"))
    )
    (net (code "58") (name "unconnected-(IC1-PB13-Pad26)") (class "Default")
      (node (ref "IC1") (pin "26") (pinfunction "PB13_26") (pintype "bidirectional+no_connect"))
    )
    (net (code "59") (name "unconnected-(IC1-PB14-Pad27)") (class "Default")
      (node (ref "IC1") (pin "27") (pinfunction "PB14_27") (pintype "bidirectional+no_connect"))
    )
    (net (code "60") (name "unconnected-(IC1-PB15-Pad28)") (class "Default")
      (node (ref "IC1") (pin "28") (pinfunction "PB15_28") (pintype "bidirectional+no_connect"))
    )
    (net (code "61") (name "unconnected-(IC1-PC13-TAMPER-RTC-Pad2)") (class "Default")
      (node (ref "IC1") (pin "2") (pinfunction "PC13-TAMPER-RTC_2") (pintype "bidirectional+no_connect"))
    )
    (net (code "62") (name "unconnected-(K1-I{slash}O1-Pad1)") (class "Default")
      (node (ref "K1") (pin "1") (pinfunction "I/O1_1") (pintype "passive+no_connect"))
    )
    (net (code "63") (name "unconnected-(K1-I{slash}O2-Pad4)") (class "Default")
      (node (ref "K1") (pin "4") (pinfunction "I/O2_4") (pintype "passive+no_connect"))
    )
    (net (code "64") (name "unconnected-(K1-I{slash}O2-Pad6)") (class "Default")
      (node (ref "K1") (pin "6") (pinfunction "I/O2_6") (pintype "passive+no_connect"))
    )
    (net (code "65") (name "unconnected-(K1-TAP2-Pad5)") (class "Default")
      (node (ref "K1") (pin "5") (pinfunction "TAP2_5") (pintype "passive+no_connect"))
    )
  )
)
